# CONFIG.net
KiCad netlist of a schematic drawn in Altium Designer
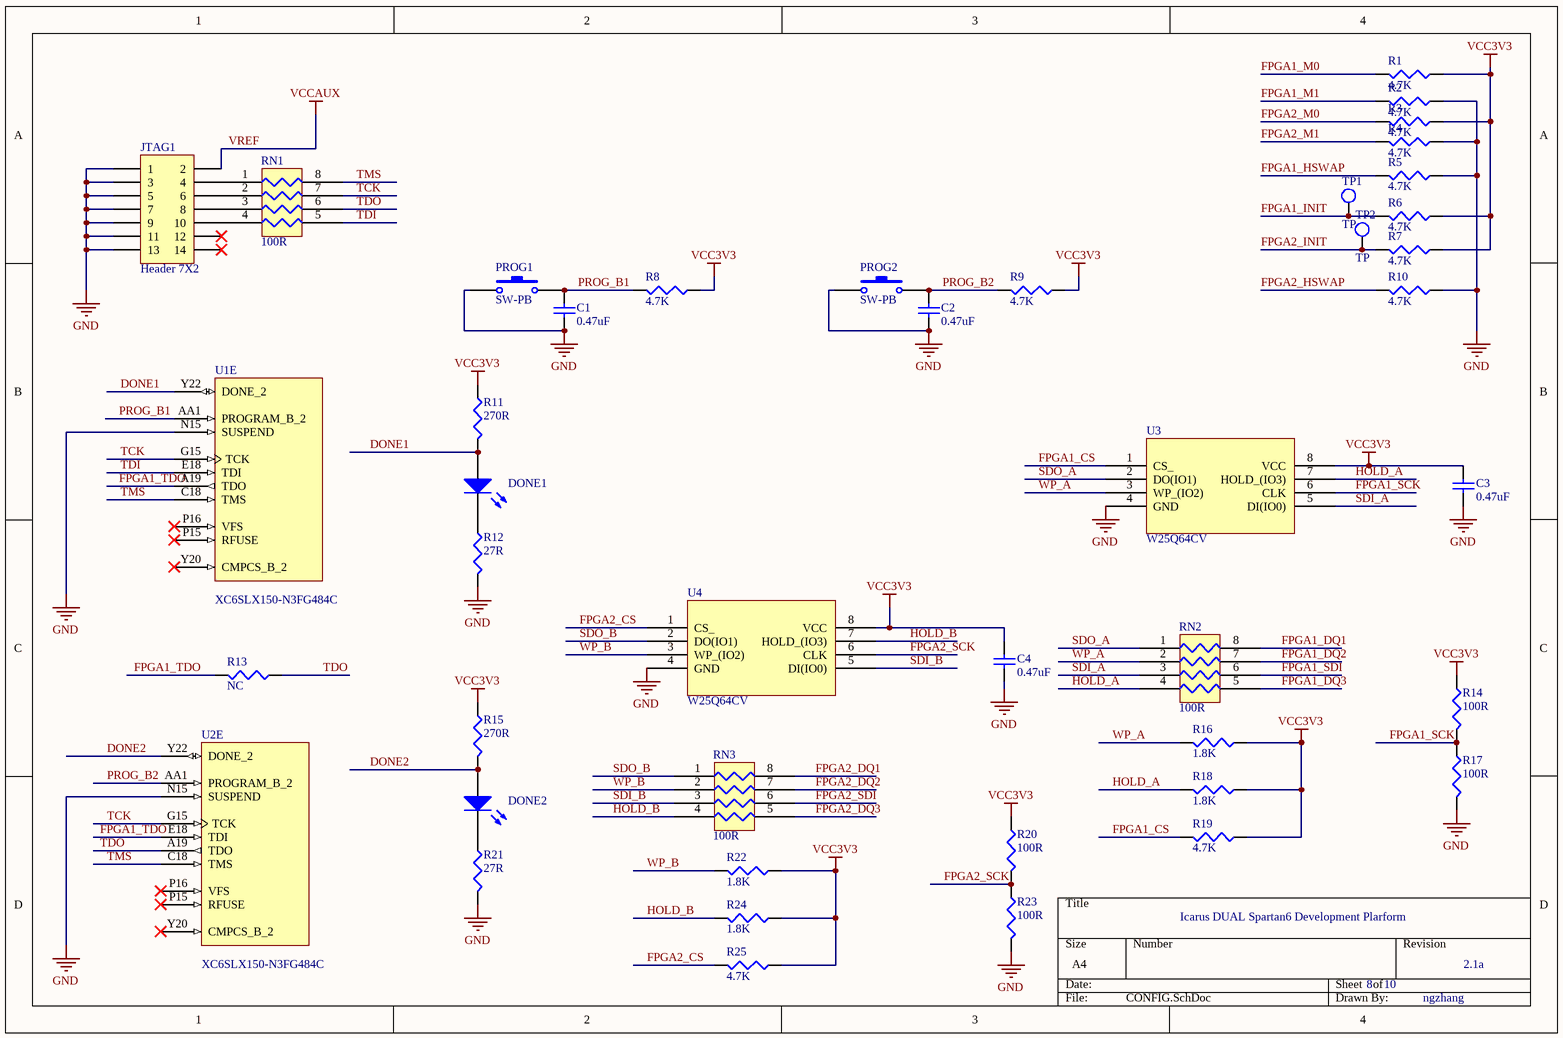
[diagram p0: CONFIG.SchDoc]

(export (version "E")
  (design (tool "Eeschema 10.0.6"))
  (components
    (comp (ref "C1")
      (value "0.47uF")
      (footprint "0402")
      (description "Capacitor (Semiconductor SIM Model)")
      (fields (field (name "PUBLISHER") "Altium Limited"))
      (libsource (lib "Miscellaneous Devices") (part "Cap Semi"))
    )
    (comp (ref "C2")
      (value "0.47uF")
      (footprint "0402")
      (description "Capacitor (Semiconductor SIM Model)")
      (fields (field (name "PUBLISHER") "Altium Limited"))
      (libsource (lib "Miscellaneous Devices") (part "Cap Semi"))
    )
    (comp (ref "C3")
      (value "0.47uF")
      (footprint "0402")
      (description "Capacitor (Semiconductor SIM Model)")
      (fields (field (name "PUBLISHER") "Altium Limited"))
      (libsource (lib "Miscellaneous Devices") (part "Cap Semi"))
    )
    (comp (ref "C4")
      (value "0.47uF")
      (footprint "0402")
      (description "Capacitor (Semiconductor SIM Model)")
      (fields (field (name "PUBLISHER") "Altium Limited"))
      (libsource (lib "Miscellaneous Devices") (part "Cap Semi"))
    )
    (comp (ref "DONE1")
      (value "LED3")
      (footprint "CD1608-0603")
      (description "Typical BLUE SiC LED")
      (fields (field (name "PUBLISHER") "Altium Limited"))
      (libsource (lib "Miscellaneous Devices") (part "LED3"))
    )
    (comp (ref "DONE2")
      (value "LED3")
      (footprint "CD1608-0603")
      (description "Typical BLUE SiC LED")
      (fields (field (name "PUBLISHER") "Altium Limited"))
      (libsource (lib "Miscellaneous Devices") (part "LED3"))
    )
    (comp (ref "JTAG1")
      (value "Header 7X2")
      (footprint "MOLEX14P")
      (description "Header, 7-Pin, Dual row")
      (fields (field (name "PUBLISHER") "Altium Limited"))
      (libsource (lib "Miscellaneous Connectors") (part "Header 7X2"))
    )
    (comp (ref "PROG1")
      (value "SW-PB")
      (footprint "SW_2")
      (description "Switch")
      (fields (field (name "PUBLISHER") "Altium Limited"))
      (libsource (lib "Miscellaneous Devices") (part "SW-PB"))
    )
    (comp (ref "PROG2")
      (value "SW-PB")
      (footprint "SW_2")
      (description "Switch")
      (fields (field (name "PUBLISHER") "Altium Limited"))
      (libsource (lib "Miscellaneous Devices") (part "SW-PB"))
    )
    (comp (ref "R1")
      (value "4.7K")
      (footprint "0402")
      (description "Resistor")
      (fields (field (name "PUBLISHER") "Altium Limited"))
      (libsource (lib "Miscellaneous Devices") (part "Res3"))
    )
    (comp (ref "R2")
      (value "4.7K")
      (footprint "0402")
      (description "Resistor")
      (fields (field (name "PUBLISHER") "Altium Limited"))
      (libsource (lib "Miscellaneous Devices") (part "Res3"))
    )
    (comp (ref "R3")
      (value "4.7K")
      (footprint "0402")
      (description "Resistor")
      (fields (field (name "PUBLISHER") "Altium Limited"))
      (libsource (lib "Miscellaneous Devices") (part "Res3"))
    )
    (comp (ref "R4")
      (value "4.7K")
      (footprint "0402")
      (description "Resistor")
      (fields (field (name "PUBLISHER") "Altium Limited"))
      (libsource (lib "Miscellaneous Devices") (part "Res3"))
    )
    (comp (ref "R5")
      (value "4.7K")
      (footprint "0402")
      (description "Resistor")
      (fields (field (name "PUBLISHER") "Altium Limited"))
      (libsource (lib "Miscellaneous Devices") (part "Res3"))
    )
    (comp (ref "R6")
      (value "4.7K")
      (footprint "0402")
      (description "Resistor")
      (fields (field (name "PUBLISHER") "Altium Limited"))
      (libsource (lib "Miscellaneous Devices") (part "Res3"))
    )
    (comp (ref "R7")
      (value "4.7K")
      (footprint "0402")
      (description "Resistor")
      (fields (field (name "PUBLISHER") "Altium Limited"))
      (libsource (lib "Miscellaneous Devices") (part "Res3"))
    )
    (comp (ref "R8")
      (value "4.7K")
      (footprint "0402")
      (description "Resistor")
      (fields (field (name "PUBLISHER") "Altium Limited"))
      (libsource (lib "Miscellaneous Devices") (part "Res3"))
    )
    (comp (ref "R9")
      (value "4.7K")
      (footprint "0402")
      (description "Resistor")
      (fields (field (name "PUBLISHER") "Altium Limited"))
      (libsource (lib "Miscellaneous Devices") (part "Res3"))
    )
    (comp (ref "R10")
      (value "4.7K")
      (footprint "0402")
      (description "Resistor")
      (fields (field (name "PUBLISHER") "Altium Limited"))
      (libsource (lib "Miscellaneous Devices") (part "Res3"))
    )
    (comp (ref "R11")
      (value "270R")
      (footprint "0402")
      (description "Resistor")
      (fields (field (name "PUBLISHER") "Altium Limited"))
      (libsource (lib "Miscellaneous Devices") (part "Res3"))
    )
    (comp (ref "R12")
      (value "27R")
      (footprint "0402")
      (description "Resistor")
      (fields (field (name "PUBLISHER") "Altium Limited"))
      (libsource (lib "Miscellaneous Devices") (part "Res3"))
    )
    (comp (ref "R13")
      (value "NC")
      (footprint "0402")
      (description "Resistor")
      (fields (field (name "PUBLISHER") "Altium Limited"))
      (libsource (lib "Miscellaneous Devices") (part "Res3"))
    )
    (comp (ref "R14")
      (value "100R")
      (footprint "0402")
      (description "Resistor")
      (fields (field (name "PUBLISHER") "Altium Limited"))
      (libsource (lib "Miscellaneous Devices") (part "Res3"))
    )
    (comp (ref "R15")
      (value "270R")
      (footprint "0402")
      (description "Resistor")
      (fields (field (name "PUBLISHER") "Altium Limited"))
      (libsource (lib "Miscellaneous Devices") (part "Res3"))
    )
    (comp (ref "R16")
      (value "1.8K")
      (footprint "0402")
      (description "Resistor")
      (fields (field (name "PUBLISHER") "Altium Limited"))
      (libsource (lib "Miscellaneous Devices") (part "Res3"))
    )
    (comp (ref "R17")
      (value "100R")
      (footprint "0402")
      (description "Resistor")
      (fields (field (name "PUBLISHER") "Altium Limited"))
      (libsource (lib "Miscellaneous Devices") (part "Res3"))
    )
    (comp (ref "R18")
      (value "1.8K")
      (footprint "0402")
      (description "Resistor")
      (fields (field (name "PUBLISHER") "Altium Limited"))
      (libsource (lib "Miscellaneous Devices") (part "Res3"))
    )
    (comp (ref "R19")
      (value "4.7K")
      (footprint "0402")
      (description "Resistor")
      (fields (field (name "PUBLISHER") "Altium Limited"))
      (libsource (lib "Miscellaneous Devices") (part "Res3"))
    )
    (comp (ref "R20")
      (value "100R")
      (footprint "0402")
      (description "Resistor")
      (fields (field (name "PUBLISHER") "Altium Limited"))
      (libsource (lib "Miscellaneous Devices") (part "Res3"))
    )
    (comp (ref "R21")
      (value "27R")
      (footprint "0402")
      (description "Resistor")
      (fields (field (name "PUBLISHER") "Altium Limited"))
      (libsource (lib "Miscellaneous Devices") (part "Res3"))
    )
    (comp (ref "R22")
      (value "1.8K")
      (footprint "0402")
      (description "Resistor")
      (fields (field (name "PUBLISHER") "Altium Limited"))
      (libsource (lib "Miscellaneous Devices") (part "Res3"))
    )
    (comp (ref "R23")
      (value "100R")
      (footprint "0402")
      (description "Resistor")
      (fields (field (name "PUBLISHER") "Altium Limited"))
      (libsource (lib "Miscellaneous Devices") (part "Res3"))
    )
    (comp (ref "R24")
      (value "1.8K")
      (footprint "0402")
      (description "Resistor")
      (fields (field (name "PUBLISHER") "Altium Limited"))
      (libsource (lib "Miscellaneous Devices") (part "Res3"))
    )
    (comp (ref "R25")
      (value "4.7K")
      (footprint "0402")
      (description "Resistor")
      (fields (field (name "PUBLISHER") "Altium Limited"))
      (libsource (lib "Miscellaneous Devices") (part "Res3"))
    )
    (comp (ref "RN1") (value "100R") (footprint "EXBV8V") (libsource (lib "S6") (part "RES4PACK")))
    (comp (ref "RN2") (value "100R") (footprint "EXBV8V") (libsource (lib "S6") (part "RES4PACK")))
    (comp (ref "RN3") (value "100R") (footprint "EXBV8V") (libsource (lib "S6") (part "RES4PACK")))
    (comp (ref "TP1") (value "TP") (footprint "TP") (libsource (lib "S6") (part "TP")))
    (comp (ref "TP2") (value "TP") (footprint "TP") (libsource (lib "S6") (part "TP")))
    (comp (ref "U1")
      (value "XC6SLX150-N3FG484C")
      (footprint "FG484")
      (fields (field (name "PUBLISHER") "Altium Limited"))
      (libsource (lib "Xilinx Spartan-6") (part "XC6SLX150-N3FG484C"))
    )
    (comp (ref "U2")
      (value "XC6SLX150-N3FG484C")
      (footprint "FG484")
      (fields (field (name "PUBLISHER") "Altium Limited"))
      (libsource (lib "Xilinx Spartan-6") (part "XC6SLX150-N3FG484C"))
    )
    (comp (ref "U3") (value "W25Q64CV") (footprint "WSON6X5") (libsource (lib "S6") (part "W25Q64CV")))
    (comp (ref "U4") (value "W25Q64CV") (footprint "WSON6X5") (libsource (lib "S6") (part "W25Q64CV")))
  )
  (nets
    (net (code "1") (name "/DONE1") (class "Default")
      (node (ref "DONE1") (pin "1") (pinfunction "A_1") (pintype "passive"))
      (node (ref "R11") (pin "2") (pinfunction "2_2") (pintype "passive"))
      (node (ref "U1") (pin "Y22") (pinfunction "DONE_2_Y22") (pintype "bidirectional"))
    )
    (net (code "2") (name "/DONE2") (class "Default")
      (node (ref "DONE2") (pin "1") (pinfunction "A_1") (pintype "passive"))
      (node (ref "R15") (pin "2") (pinfunction "2_2") (pintype "passive"))
      (node (ref "U2") (pin "Y22") (pinfunction "DONE_2_Y22") (pintype "bidirectional"))
    )
    (net (code "3") (name "/FPGA1_CS") (class "Default")
      (node (ref "R19") (pin "2") (pinfunction "2_2") (pintype "passive"))
      (node (ref "U3") (pin "1") (pinfunction "CS__1") (pintype "passive"))
    )
    (net (code "4") (name "/FPGA1_DQ1") (class "Default")
      (node (ref "RN2") (pin "8") (pinfunction "8_8") (pintype "power_in"))
    )
    (net (code "5") (name "/FPGA1_DQ2") (class "Default")
      (node (ref "RN2") (pin "7") (pinfunction "7_7") (pintype "power_in"))
    )
    (net (code "6") (name "/FPGA1_DQ3") (class "Default")
      (node (ref "RN2") (pin "5") (pinfunction "5_5") (pintype "power_in"))
    )
    (net (code "7") (name "/FPGA1_HSWAP") (class "Default")
      (node (ref "R5") (pin "2") (pinfunction "2_2") (pintype "passive"))
    )
    (net (code "8") (name "/FPGA1_INIT") (class "Default")
      (node (ref "R6") (pin "2") (pinfunction "2_2") (pintype "passive"))
      (node (ref "TP1") (pin "1") (pinfunction "TP_1") (pintype "passive"))
    )
    (net (code "9") (name "/FPGA1_M0") (class "Default")
      (node (ref "R1") (pin "2") (pinfunction "2_2") (pintype "passive"))
    )
    (net (code "10") (name "/FPGA1_M1") (class "Default")
      (node (ref "R2") (pin "2") (pinfunction "2_2") (pintype "passive"))
    )
    (net (code "11") (name "/FPGA1_SCK") (class "Default")
      (node (ref "R14") (pin "2") (pinfunction "2_2") (pintype "passive"))
      (node (ref "R17") (pin "1") (pinfunction "1_1") (pintype "passive"))
      (node (ref "U3") (pin "6") (pinfunction "CLK_6") (pintype "passive"))
    )
    (net (code "12") (name "/FPGA1_SDI") (class "Default")
      (node (ref "RN2") (pin "6") (pinfunction "6_6") (pintype "power_in"))
    )
    (net (code "13") (name "/FPGA1_TDO") (class "Default")
      (node (ref "R13") (pin "2") (pinfunction "2_2") (pintype "passive"))
      (node (ref "U1") (pin "A19") (pinfunction "TDO_A19") (pintype "output"))
      (node (ref "U2") (pin "E18") (pinfunction "TDI_E18") (pintype "input"))
    )
    (net (code "14") (name "/FPGA2_CS") (class "Default")
      (node (ref "R25") (pin "2") (pinfunction "2_2") (pintype "passive"))
      (node (ref "U4") (pin "1") (pinfunction "CS__1") (pintype "passive"))
    )
    (net (code "15") (name "/FPGA2_DQ1") (class "Default")
      (node (ref "RN3") (pin "8") (pinfunction "8_8") (pintype "power_in"))
    )
    (net (code "16") (name "/FPGA2_DQ2") (class "Default")
      (node (ref "RN3") (pin "7") (pinfunction "7_7") (pintype "power_in"))
    )
    (net (code "17") (name "/FPGA2_DQ3") (class "Default")
      (node (ref "RN3") (pin "5") (pinfunction "5_5") (pintype "power_in"))
    )
    (net (code "18") (name "/FPGA2_HSWAP") (class "Default")
      (node (ref "R10") (pin "2") (pinfunction "2_2") (pintype "passive"))
    )
    (net (code "19") (name "/FPGA2_INIT") (class "Default")
      (node (ref "R7") (pin "2") (pinfunction "2_2") (pintype "passive"))
      (node (ref "TP2") (pin "1") (pinfunction "TP_1") (pintype "passive"))
    )
    (net (code "20") (name "/FPGA2_M0") (class "Default")
      (node (ref "R3") (pin "2") (pinfunction "2_2") (pintype "passive"))
    )
    (net (code "21") (name "/FPGA2_M1") (class "Default")
      (node (ref "R4") (pin "2") (pinfunction "2_2") (pintype "passive"))
    )
    (net (code "22") (name "/FPGA2_SCK") (class "Default")
      (node (ref "R20") (pin "2") (pinfunction "2_2") (pintype "passive"))
      (node (ref "R23") (pin "1") (pinfunction "1_1") (pintype "passive"))
      (node (ref "U4") (pin "6") (pinfunction "CLK_6") (pintype "passive"))
    )
    (net (code "23") (name "/FPGA2_SDI") (class "Default")
      (node (ref "RN3") (pin "6") (pinfunction "6_6") (pintype "power_in"))
    )
    (net (code "24") (name "/HOLD_A") (class "Default")
      (node (ref "R18") (pin "2") (pinfunction "2_2") (pintype "passive"))
      (node (ref "RN2") (pin "4") (pinfunction "4_4") (pintype "power_in"))
      (node (ref "U3") (pin "7") (pinfunction "HOLD_(IO3)_7") (pintype "passive"))
    )
    (net (code "25") (name "/HOLD_B") (class "Default")
      (node (ref "R24") (pin "2") (pinfunction "2_2") (pintype "passive"))
      (node (ref "RN3") (pin "4") (pinfunction "4_4") (pintype "power_in"))
      (node (ref "U4") (pin "7") (pinfunction "HOLD_(IO3)_7") (pintype "passive"))
    )
    (net (code "26") (name "/PROG_B1") (class "Default")
      (node (ref "C1") (pin "1") (pinfunction "1_1") (pintype "passive"))
      (node (ref "PROG1") (pin "2") (pinfunction "2_2") (pintype "passive"))
      (node (ref "R8") (pin "2") (pinfunction "2_2") (pintype "passive"))
      (node (ref "U1") (pin "AA1") (pinfunction "PROGRAM_B_2_AA1") (pintype "input"))
    )
    (net (code "27") (name "/PROG_B2") (class "Default")
      (node (ref "C2") (pin "1") (pinfunction "1_1") (pintype "passive"))
      (node (ref "PROG2") (pin "2") (pinfunction "2_2") (pintype "passive"))
      (node (ref "R9") (pin "2") (pinfunction "2_2") (pintype "passive"))
      (node (ref "U2") (pin "AA1") (pinfunction "PROGRAM_B_2_AA1") (pintype "input"))
    )
    (net (code "28") (name "/SDI_A") (class "Default")
      (node (ref "RN2") (pin "3") (pinfunction "3_3") (pintype "power_in"))
      (node (ref "U3") (pin "5") (pinfunction "DI(IO0)_5") (pintype "passive"))
    )
    (net (code "29") (name "/SDI_B") (class "Default")
      (node (ref "RN3") (pin "3") (pinfunction "3_3") (pintype "power_in"))
      (node (ref "U4") (pin "5") (pinfunction "DI(IO0)_5") (pintype "passive"))
    )
    (net (code "30") (name "/SDO_A") (class "Default")
      (node (ref "RN2") (pin "1") (pinfunction "1_1") (pintype "power_in"))
      (node (ref "U3") (pin "2") (pinfunction "DO(IO1)_2") (pintype "passive"))
    )
    (net (code "31") (name "/SDO_B") (class "Default")
      (node (ref "RN3") (pin "1") (pinfunction "1_1") (pintype "power_in"))
      (node (ref "U4") (pin "2") (pinfunction "DO(IO1)_2") (pintype "passive"))
    )
    (net (code "32") (name "/TCK") (class "Default")
      (node (ref "RN1") (pin "7") (pinfunction "7_7") (pintype "power_in"))
      (node (ref "U1") (pin "G15") (pinfunction "TCK_G15") (pintype "input"))
      (node (ref "U2") (pin "G15") (pinfunction "TCK_G15") (pintype "input"))
    )
    (net (code "33") (name "/TDI") (class "Default")
      (node (ref "RN1") (pin "5") (pinfunction "5_5") (pintype "power_in"))
      (node (ref "U1") (pin "E18") (pinfunction "TDI_E18") (pintype "input"))
    )
    (net (code "34") (name "/TDO") (class "Default")
      (node (ref "R13") (pin "1") (pinfunction "1_1") (pintype "passive"))
      (node (ref "RN1") (pin "6") (pinfunction "6_6") (pintype "power_in"))
      (node (ref "U2") (pin "A19") (pinfunction "TDO_A19") (pintype "output"))
    )
    (net (code "35") (name "/TMS") (class "Default")
      (node (ref "RN1") (pin "8") (pinfunction "8_8") (pintype "power_in"))
      (node (ref "U1") (pin "C18") (pinfunction "TMS_C18") (pintype "input"))
      (node (ref "U2") (pin "C18") (pinfunction "TMS_C18") (pintype "input"))
    )
    (net (code "36") (name "/WP_A") (class "Default")
      (node (ref "R16") (pin "2") (pinfunction "2_2") (pintype "passive"))
      (node (ref "RN2") (pin "2") (pinfunction "2_2") (pintype "power_in"))
      (node (ref "U3") (pin "3") (pinfunction "WP_(IO2)_3") (pintype "passive"))
    )
    (net (code "37") (name "/WP_B") (class "Default")
      (node (ref "R22") (pin "2") (pinfunction "2_2") (pintype "passive"))
      (node (ref "RN3") (pin "2") (pinfunction "2_2") (pintype "power_in"))
      (node (ref "U4") (pin "3") (pinfunction "WP_(IO2)_3") (pintype "passive"))
    )
    (net (code "38") (name "GND") (class "Default")
      (node (ref "C1") (pin "2") (pinfunction "2_2") (pintype "passive"))
      (node (ref "C2") (pin "2") (pinfunction "2_2") (pintype "passive"))
      (node (ref "C3") (pin "1") (pinfunction "1_1") (pintype "passive"))
      (node (ref "C4") (pin "1") (pinfunction "1_1") (pintype "passive"))
      (node (ref "JTAG1") (pin "1") (pinfunction "1_1") (pintype "passive"))
      (node (ref "JTAG1") (pin "11") (pinfunction "11_11") (pintype "passive"))
      (node (ref "JTAG1") (pin "13") (pinfunction "13_13") (pintype "passive"))
      (node (ref "JTAG1") (pin "3") (pinfunction "3_3") (pintype "passive"))
      (node (ref "JTAG1") (pin "5") (pinfunction "5_5") (pintype "passive"))
      (node (ref "JTAG1") (pin "7") (pinfunction "7_7") (pintype "passive"))
      (node (ref "JTAG1") (pin "9") (pinfunction "9_9") (pintype "passive"))
      (node (ref "PROG1") (pin "1") (pinfunction "1_1") (pintype "passive"))
      (node (ref "PROG2") (pin "1") (pinfunction "1_1") (pintype "passive"))
      (node (ref "R10") (pin "1") (pinfunction "1_1") (pintype "passive"))
      (node (ref "R12") (pin "2") (pinfunction "2_2") (pintype "passive"))
      (node (ref "R17") (pin "2") (pinfunction "2_2") (pintype "passive"))
      (node (ref "R2") (pin "1") (pinfunction "1_1") (pintype "passive"))
      (node (ref "R21") (pin "2") (pinfunction "2_2") (pintype "passive"))
      (node (ref "R23") (pin "2") (pinfunction "2_2") (pintype "passive"))
      (node (ref "R4") (pin "1") (pinfunction "1_1") (pintype "passive"))
      (node (ref "R5") (pin "1") (pinfunction "1_1") (pintype "passive"))
      (node (ref "U1") (pin "N15") (pinfunction "SUSPEND_N15") (pintype "input"))
      (node (ref "U2") (pin "N15") (pinfunction "SUSPEND_N15") (pintype "input"))
      (node (ref "U3") (pin "4") (pinfunction "GND_4") (pintype "passive"))
      (node (ref "U4") (pin "4") (pinfunction "GND_4") (pintype "passive"))
    )
    (net (code "39") (name "Net-(DONE1-K)") (class "Default")
      (node (ref "DONE1") (pin "2") (pinfunction "K_2") (pintype "passive"))
      (node (ref "R12") (pin "1") (pinfunction "1_1") (pintype "passive"))
    )
    (net (code "40") (name "Net-(DONE2-K)") (class "Default")
      (node (ref "DONE2") (pin "2") (pinfunction "K_2") (pintype "passive"))
      (node (ref "R21") (pin "1") (pinfunction "1_1") (pintype "passive"))
    )
    (net (code "41") (name "Net-(JTAG1-Pad4)") (class "Default")
      (node (ref "JTAG1") (pin "4") (pinfunction "4_4") (pintype "passive"))
      (node (ref "RN1") (pin "1") (pinfunction "1_1") (pintype "power_in"))
    )
    (net (code "42") (name "Net-(JTAG1-Pad6)") (class "Default")
      (node (ref "JTAG1") (pin "6") (pinfunction "6_6") (pintype "passive"))
      (node (ref "RN1") (pin "2") (pinfunction "2_2") (pintype "power_in"))
    )
    (net (code "43") (name "Net-(JTAG1-Pad8)") (class "Default")
      (node (ref "JTAG1") (pin "8") (pinfunction "8_8") (pintype "passive"))
      (node (ref "RN1") (pin "3") (pinfunction "3_3") (pintype "power_in"))
    )
    (net (code "44") (name "Net-(JTAG1-Pad10)") (class "Default")
      (node (ref "JTAG1") (pin "10") (pinfunction "10_10") (pintype "passive"))
      (node (ref "RN1") (pin "4") (pinfunction "4_4") (pintype "power_in"))
    )
    (net (code "45") (name "VCC3V3") (class "Default")
      (node (ref "C3") (pin "2") (pinfunction "2_2") (pintype "passive"))
      (node (ref "C4") (pin "2") (pinfunction "2_2") (pintype "passive"))
      (node (ref "R1") (pin "1") (pinfunction "1_1") (pintype "passive"))
      (node (ref "R11") (pin "1") (pinfunction "1_1") (pintype "passive"))
      (node (ref "R14") (pin "1") (pinfunction "1_1") (pintype "passive"))
      (node (ref "R15") (pin "1") (pinfunction "1_1") (pintype "passive"))
      (node (ref "R16") (pin "1") (pinfunction "1_1") (pintype "passive"))
      (node (ref "R18") (pin "1") (pinfunction "1_1") (pintype "passive"))
      (node (ref "R19") (pin "1") (pinfunction "1_1") (pintype "passive"))
      (node (ref "R20") (pin "1") (pinfunction "1_1") (pintype "passive"))
      (node (ref "R22") (pin "1") (pinfunction "1_1") (pintype "passive"))
      (node (ref "R24") (pin "1") (pinfunction "1_1") (pintype "passive"))
      (node (ref "R25") (pin "1") (pinfunction "1_1") (pintype "passive"))
      (node (ref "R3") (pin "1") (pinfunction "1_1") (pintype "passive"))
      (node (ref "R6") (pin "1") (pinfunction "1_1") (pintype "passive"))
      (node (ref "R7") (pin "1") (pinfunction "1_1") (pintype "passive"))
      (node (ref "R8") (pin "1") (pinfunction "1_1") (pintype "passive"))
      (node (ref "R9") (pin "1") (pinfunction "1_1") (pintype "passive"))
      (node (ref "U3") (pin "8") (pinfunction "VCC_8") (pintype "passive"))
      (node (ref "U4") (pin "8") (pinfunction "VCC_8") (pintype "passive"))
    )
    (net (code "46") (name "VCCAUX") (class "Default")
      (node (ref "JTAG1") (pin "2") (pinfunction "2_2") (pintype "passive"))
    )
    (net (code "47") (name "unconnected-(JTAG1-Pad12)") (class "Default")
      (node (ref "JTAG1") (pin "12") (pinfunction "12_12") (pintype "passive+no_connect"))
    )
    (net (code "48") (name "unconnected-(JTAG1-Pad14)") (class "Default")
      (node (ref "JTAG1") (pin "14") (pinfunction "14_14") (pintype "passive+no_connect"))
    )
    (net (code "49") (name "unconnected-(U1E-CMPCS_B_2-PadY20)") (class "Default")
      (node (ref "U1") (pin "Y20") (pinfunction "CMPCS_B_2_Y20") (pintype "input+no_connect"))
    )
    (net (code "50") (name "unconnected-(U1E-RFUSE-PadP15)") (class "Default")
      (node (ref "U1") (pin "P15") (pinfunction "RFUSE_P15") (pintype "input+no_connect"))
    )
    (net (code "51") (name "unconnected-(U1E-VFS-PadP16)") (class "Default")
      (node (ref "U1") (pin "P16") (pinfunction "VFS_P16") (pintype "input+no_connect"))
    )
    (net (code "52") (name "unconnected-(U2E-CMPCS_B_2-PadY20)") (class "Default")
      (node (ref "U2") (pin "Y20") (pinfunction "CMPCS_B_2_Y20") (pintype "input+no_connect"))
    )
    (net (code "53") (name "unconnected-(U2E-RFUSE-PadP15)") (class "Default")
      (node (ref "U2") (pin "P15") (pinfunction "RFUSE_P15") (pintype "input+no_connect"))
    )
    (net (code "54") (name "unconnected-(U2E-VFS-PadP16)") (class "Default")
      (node (ref "U2") (pin "P16") (pinfunction "VFS_P16") (pintype "input+no_connect"))
    )
  )
)
